# AstroEQ_Arduino_Mega.net
KiCad netlist of a schematic drawn in EAGLE
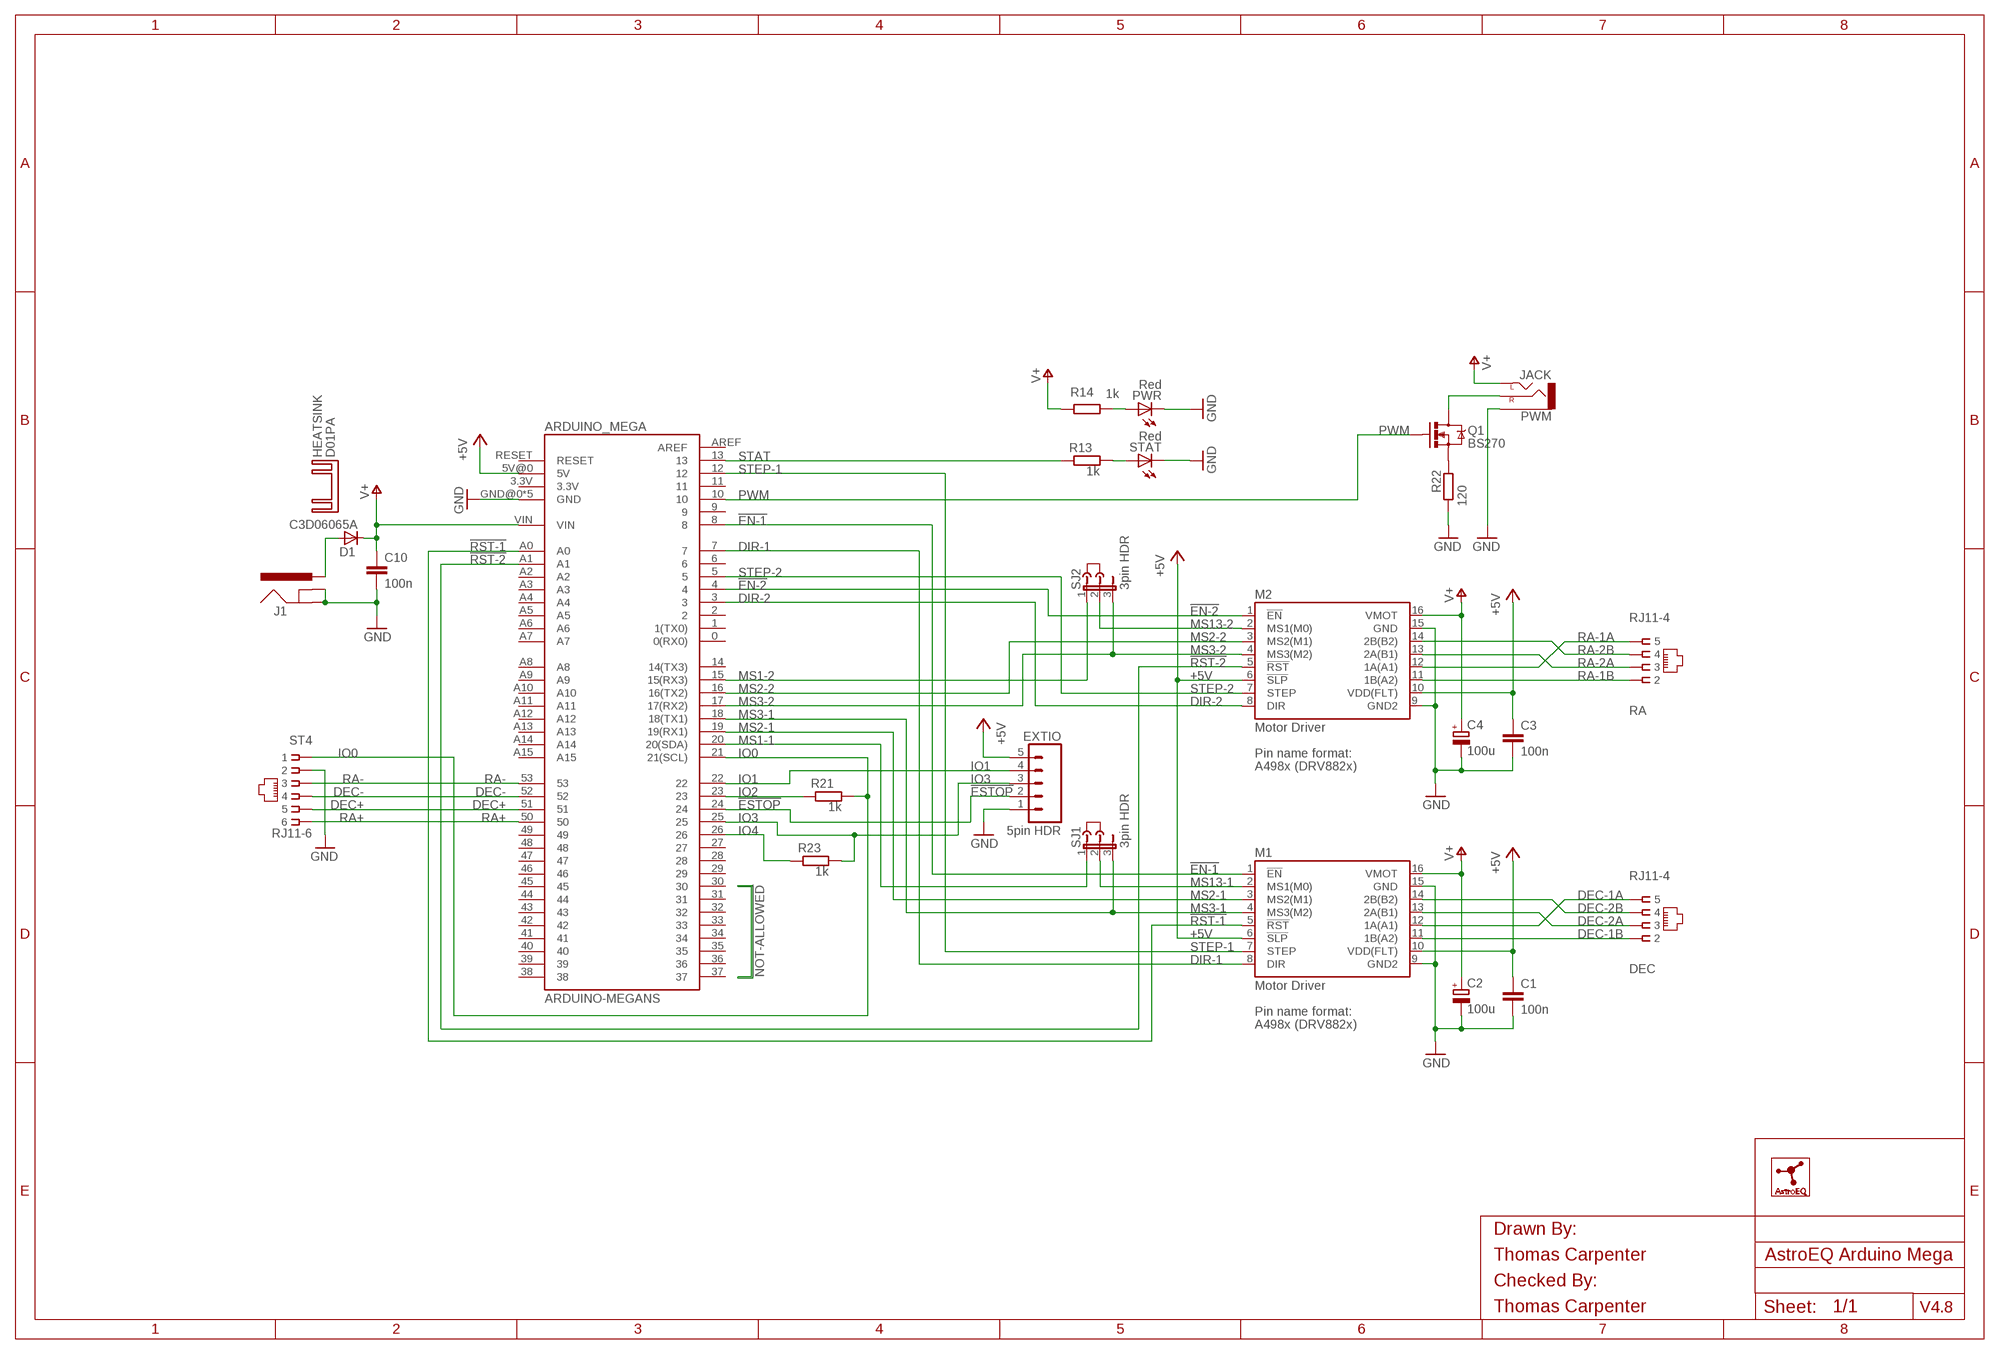
[diagram p0: schematic, sheet 1]

(export (version "E")
  (design (tool "Eeschema 10.0.6"))
  (components
    (comp (ref "ARDUINO_MEGA")
      (value "ARDUINO-MEGANS")
      (footprint "eagle-import:ARDUINO_MEGA_NS")
      (libsource (lib "eagle-import") (part "ARDUINO-MEGANS"))
    )
    (comp (ref "C1")
      (value "100n")
      (footprint "eagle-import:C025-024X044")
      (fields (field (name "MF") "AVX") (field (name "MPN") "SR205C104KAR"))
      (libsource (lib "eagle-import") (part "C-EU025-024X044"))
    )
    (comp (ref "C2")
      (value "100u")
      (footprint "eagle-import:E2,5-7")
      (fields (field (name "MF") "MULTICOMP") (field (name "MPN") "MCGPR25V107M6.3X11"))
      (libsource (lib "eagle-import") (part "CPOL-EUE2.5-7"))
    )
    (comp (ref "C3")
      (value "100n")
      (footprint "eagle-import:C025-024X044")
      (fields (field (name "MF") "AVX") (field (name "MPN") "SR205C104KAR"))
      (libsource (lib "eagle-import") (part "C-EU025-024X044"))
    )
    (comp (ref "C4")
      (value "100u")
      (footprint "eagle-import:E2,5-7")
      (fields (field (name "MF") "MULTICOMP") (field (name "MPN") "MCGPR25V107M6.3X11"))
      (libsource (lib "eagle-import") (part "CPOL-EUE2.5-7"))
    )
    (comp (ref "C10")
      (value "100n")
      (footprint "eagle-import:C025-024X044")
      (fields (field (name "MF") "AVX") (field (name "MPN") "SR205C104KAR"))
      (libsource (lib "eagle-import") (part "C-EU025-024X044"))
    )
    (comp (ref "D1")
      (value "C3D06065A")
      (footprint "eagle-import:TO220ACS")
      (fields (field (name "MF") "CREE"))
      (libsource (lib "eagle-import") (part "MUR820VERT"))
    )
    (comp (ref "DEC")
      (value "RJ11-4")
      (footprint "eagle-import:RJ11-NO_SHIELD-4")
      (fields (field (name "MF") "MOLEX") (field (name "MPN") "95501-2641"))
      (libsource (lib "eagle-import") (part "RJ11-4"))
    )
    (comp (ref "EXTIO")
      (value "5pin HDR")
      (footprint "eagle-import:1X05")
      (libsource (lib "eagle-import") (part "M05PTH"))
    )
    (comp (ref "HEATSINK")
      (value "D01PA")
      (footprint "eagle-import:D01PA")
      (libsource (lib "eagle-import") (part "D01PA"))
    )
    (comp (ref "J1")
      (value "POWER_JACKPTH")
      (footprint "eagle-import:POWER_JACK_PTH")
      (fields (field (name "MF") "MULTICOMP") (field (name "MPN") "MJ-179PH"))
      (libsource (lib "eagle-import") (part "POWER_JACKPTH"))
    )
    (comp (ref "J2")
      (value "DNI")
      (footprint "eagle-import:JUMP")
      (fields (field (name "MF") "3M") (field (name "MPN") "969102-0000-DA"))
      (libsource (lib "eagle-import") (part "JUMPER"))
    )
    (comp (ref "J3")
      (value "DNI")
      (footprint "eagle-import:JUMP")
      (fields (field (name "MF") "3M") (field (name "MPN") "969102-0000-DA"))
      (libsource (lib "eagle-import") (part "JUMPER"))
    )
    (comp (ref "LOGO1")
      (value "ASTROEQ8MM")
      (footprint "eagle-import:ASTROEQ")
      (libsource (lib "eagle-import") (part "ASTROEQ8MM"))
    )
    (comp (ref "M1")
      (value "Motor Driver")
      (footprint "eagle-import:DIP16-W")
      (fields (field (name "MF") "SAMTEC") (field (name "MPN") "CES-116-01-T-S"))
      (libsource (lib "eagle-import") (part "A4983CARRIER"))
    )
    (comp (ref "M2")
      (value "Motor Driver")
      (footprint "eagle-import:DIP16-W")
      (fields (field (name "MF") "SAMTEC") (field (name "MPN") "CES-116-01-T-S"))
      (libsource (lib "eagle-import") (part "A4983CARRIER"))
    )
    (comp (ref "PWM")
      (value "JACK")
      (footprint "eagle-import:AUDIO-JACK-3.5MM-VERT")
      (fields
        (field (name "MANUFACTURER") "LUMBERG")
        (field (name "MPN") "1502 01")
        (field (name "MF") "CLIFF ELECTRONIC COMPONENTS")
      )
      (libsource (lib "eagle-import") (part "AUDIO-JACKVERT"))
    )
    (comp (ref "PWR")
      (value "Red")
      (footprint "eagle-import:LED3MM")
      (fields (field (name "MF") "KINGBRIGHT") (field (name "MPN") "L-424HDT"))
      (libsource (lib "eagle-import") (part "LED3MM"))
    )
    (comp (ref "Q1")
      (value "BS270")
      (footprint "eagle-import:TO-92")
      (fields (field (name "MF") "FAIRCHILD SEMICONDUCTOR"))
      (libsource (lib "eagle-import") (part "MOSFET-NCHANNELPTH"))
    )
    (comp (ref "R13")
      (value "1k")
      (footprint "eagle-import:0204_5")
      (fields (field (name "MF") "MULTICOMP") (field (name "MPN") "MF12 1K"))
      (libsource (lib "eagle-import") (part "R-EU_0204/5"))
    )
    (comp (ref "R14")
      (value "1k")
      (footprint "eagle-import:0204_7")
      (fields (field (name "MF") "MULTICOMP") (field (name "MPN") "MF12 1K"))
      (libsource (lib "eagle-import") (part "R-EU_0204/7"))
    )
    (comp (ref "R21")
      (value "1k")
      (footprint "eagle-import:0204_7")
      (fields (field (name "MF") "MULTICOMP") (field (name "MPN") "MF12 1K"))
      (libsource (lib "eagle-import") (part "R-EU_0204/7"))
    )
    (comp (ref "R22")
      (value "120")
      (footprint "eagle-import:0204_7")
      (fields (field (name "MF") "MULTICOMP") (field (name "MPN") "MF12 120R"))
      (libsource (lib "eagle-import") (part "R-EU_0204/7"))
    )
    (comp (ref "R23")
      (value "1k")
      (footprint "eagle-import:0204_7")
      (fields (field (name "MF") "MULTICOMP") (field (name "MPN") "MF12 1K"))
      (libsource (lib "eagle-import") (part "R-EU_0204/7"))
    )
    (comp (ref "RA")
      (value "RJ11-4")
      (footprint "eagle-import:RJ11-NO_SHIELD-4")
      (fields (field (name "MF") "MOLEX") (field (name "MPN") "95501-2641"))
      (libsource (lib "eagle-import") (part "RJ11-4"))
    )
    (comp (ref "SJ1")
      (value "3pin HDR")
      (footprint "eagle-import:JP2")
      (fields (field (name "MF") "HARWIN") (field (name "MPN") "M20-9990345."))
      (libsource (lib "eagle-import") (part "JP2E"))
    )
    (comp (ref "SJ2")
      (value "3pin HDR")
      (footprint "eagle-import:JP2")
      (fields (field (name "MF") "HARWIN") (field (name "MPN") "M20-9990345."))
      (libsource (lib "eagle-import") (part "JP2E"))
    )
    (comp (ref "ST4")
      (value "RJ11-6")
      (footprint "eagle-import:RJ11-NO_SHIELD")
      (fields (field (name "MF") "TYCO ELECTRONICS") (field (name "MPN") "RJ11-2L-B"))
      (libsource (lib "eagle-import") (part "RJ11-2L-B"))
    )
    (comp (ref "STAT")
      (value "Red")
      (footprint "eagle-import:LED3MM")
      (fields (field (name "MF") "KINGBRIGHT") (field (name "MPN") "L-424HDT"))
      (libsource (lib "eagle-import") (part "LED3MM"))
    )
  )
  (nets
    (net (code "1") (name "+5V") (class "Default")
      (node (ref "ARDUINO_MEGA") (pin "5V@0") (pinfunction "5V_5V@0") (pintype "bidirectional"))
      (node (ref "C1") (pin "1") (pinfunction "1_1") (pintype "passive"))
      (node (ref "C3") (pin "1") (pinfunction "1_1") (pintype "passive"))
      (node (ref "EXTIO") (pin "5") (pinfunction "5_5") (pintype "passive"))
      (node (ref "M1") (pin "10") (pinfunction "VDD(FLT)_10") (pintype "power_in"))
      (node (ref "M1") (pin "6") (pinfunction "~{SLP}_6") (pintype "input"))
      (node (ref "M2") (pin "10") (pinfunction "VDD(FLT)_10") (pintype "power_in"))
      (node (ref "M2") (pin "6") (pinfunction "~{SLP}_6") (pintype "input"))
    )
    (net (code "2") (name "/DEC+") (class "Default")
      (node (ref "ARDUINO_MEGA") (pin "51") (pinfunction "51_51") (pintype "bidirectional"))
      (node (ref "ST4") (pin "5") (pinfunction "5_5") (pintype "passive"))
    )
    (net (code "3") (name "/DEC-") (class "Default")
      (node (ref "ARDUINO_MEGA") (pin "52") (pinfunction "52_52") (pintype "bidirectional"))
      (node (ref "ST4") (pin "4") (pinfunction "4_4") (pintype "passive"))
    )
    (net (code "4") (name "/DEC-1A") (class "Default")
      (node (ref "DEC") (pin "5") (pinfunction "5_5") (pintype "passive"))
      (node (ref "M1") (pin "12") (pinfunction "1A(A1)_12") (pintype "output"))
    )
    (net (code "5") (name "/DEC-1B") (class "Default")
      (node (ref "DEC") (pin "2") (pinfunction "2_2") (pintype "passive"))
      (node (ref "M1") (pin "11") (pinfunction "1B(A2)_11") (pintype "output"))
    )
    (net (code "6") (name "/DEC-2A") (class "Default")
      (node (ref "DEC") (pin "3") (pinfunction "3_3") (pintype "passive"))
      (node (ref "M1") (pin "13") (pinfunction "2A(B1)_13") (pintype "output"))
    )
    (net (code "7") (name "/DEC-2B") (class "Default")
      (node (ref "DEC") (pin "4") (pinfunction "4_4") (pintype "passive"))
      (node (ref "M1") (pin "14") (pinfunction "2B(B2)_14") (pintype "output"))
    )
    (net (code "8") (name "/DIR-1") (class "Default")
      (node (ref "ARDUINO_MEGA") (pin "7") (pinfunction "7_7") (pintype "bidirectional"))
      (node (ref "M1") (pin "8") (pinfunction "DIR_8") (pintype "input"))
    )
    (net (code "9") (name "/DIR-2") (class "Default")
      (node (ref "ARDUINO_MEGA") (pin "3") (pinfunction "3_3") (pintype "bidirectional"))
      (node (ref "M2") (pin "8") (pinfunction "DIR_8") (pintype "input"))
    )
    (net (code "10") (name "/IO0") (class "Default")
      (node (ref "ARDUINO_MEGA") (pin "21") (pinfunction "21(SCL)_21") (pintype "bidirectional"))
      (node (ref "R21") (pin "2") (pinfunction "2_2") (pintype "passive"))
      (node (ref "ST4") (pin "1") (pinfunction "1_1") (pintype "passive"))
    )
    (net (code "11") (name "/IO1") (class "Default")
      (node (ref "ARDUINO_MEGA") (pin "22") (pinfunction "22_22") (pintype "bidirectional"))
      (node (ref "EXTIO") (pin "4") (pinfunction "4_4") (pintype "passive"))
    )
    (net (code "12") (name "/IO2") (class "Default")
      (node (ref "ARDUINO_MEGA") (pin "23") (pinfunction "23_23") (pintype "bidirectional"))
      (node (ref "R21") (pin "1") (pinfunction "1_1") (pintype "passive"))
    )
    (net (code "13") (name "/IO3") (class "Default")
      (node (ref "ARDUINO_MEGA") (pin "25") (pinfunction "25_25") (pintype "bidirectional"))
      (node (ref "EXTIO") (pin "3") (pinfunction "3_3") (pintype "passive"))
      (node (ref "R23") (pin "2") (pinfunction "2_2") (pintype "passive"))
    )
    (net (code "14") (name "/IO4") (class "Default")
      (node (ref "ARDUINO_MEGA") (pin "26") (pinfunction "26_26") (pintype "bidirectional"))
      (node (ref "R23") (pin "1") (pinfunction "1_1") (pintype "passive"))
    )
    (net (code "15") (name "/MS1-1") (class "Default")
      (node (ref "ARDUINO_MEGA") (pin "20") (pinfunction "20(SDA)_20") (pintype "bidirectional"))
      (node (ref "SJ1") (pin "1") (pinfunction "1_1") (pintype "passive"))
    )
    (net (code "16") (name "/MS1-2") (class "Default")
      (node (ref "ARDUINO_MEGA") (pin "15") (pinfunction "15(RX3)_15") (pintype "bidirectional"))
      (node (ref "SJ2") (pin "1") (pinfunction "1_1") (pintype "passive"))
    )
    (net (code "17") (name "/MS2-1") (class "Default")
      (node (ref "ARDUINO_MEGA") (pin "19") (pinfunction "19(RX1)_19") (pintype "bidirectional"))
      (node (ref "M1") (pin "3") (pinfunction "MS2(M1)_3") (pintype "input"))
    )
    (net (code "18") (name "/MS2-2") (class "Default")
      (node (ref "ARDUINO_MEGA") (pin "16") (pinfunction "16(TX2)_16") (pintype "bidirectional"))
      (node (ref "M2") (pin "3") (pinfunction "MS2(M1)_3") (pintype "input"))
    )
    (net (code "19") (name "/MS3-1") (class "Default")
      (node (ref "ARDUINO_MEGA") (pin "18") (pinfunction "18(TX1)_18") (pintype "bidirectional"))
      (node (ref "M1") (pin "4") (pinfunction "MS3(M2)_4") (pintype "input"))
      (node (ref "SJ1") (pin "3") (pinfunction "3_3") (pintype "passive"))
    )
    (net (code "20") (name "/MS3-2") (class "Default")
      (node (ref "ARDUINO_MEGA") (pin "17") (pinfunction "17(RX2)_17") (pintype "bidirectional"))
      (node (ref "M2") (pin "4") (pinfunction "MS3(M2)_4") (pintype "input"))
      (node (ref "SJ2") (pin "3") (pinfunction "3_3") (pintype "passive"))
    )
    (net (code "21") (name "/MS13-1") (class "Default")
      (node (ref "M1") (pin "2") (pinfunction "MS1(M0)_2") (pintype "input"))
      (node (ref "SJ1") (pin "2") (pinfunction "2_2") (pintype "passive"))
    )
    (net (code "22") (name "/MS13-2") (class "Default")
      (node (ref "M2") (pin "2") (pinfunction "MS1(M0)_2") (pintype "input"))
      (node (ref "SJ2") (pin "2") (pinfunction "2_2") (pintype "passive"))
    )
    (net (code "23") (name "/PWM") (class "Default")
      (node (ref "ARDUINO_MEGA") (pin "10") (pinfunction "10_10") (pintype "bidirectional"))
      (node (ref "Q1") (pin "2") (pinfunction "G_2") (pintype "passive"))
    )
    (net (code "24") (name "/RA+") (class "Default")
      (node (ref "ARDUINO_MEGA") (pin "50") (pinfunction "50_50") (pintype "bidirectional"))
      (node (ref "ST4") (pin "6") (pinfunction "6_6") (pintype "passive"))
    )
    (net (code "25") (name "/RA-") (class "Default")
      (node (ref "ARDUINO_MEGA") (pin "53") (pinfunction "53_53") (pintype "bidirectional"))
      (node (ref "ST4") (pin "3") (pinfunction "3_3") (pintype "passive"))
    )
    (net (code "26") (name "/RA-1A") (class "Default")
      (node (ref "M2") (pin "12") (pinfunction "1A(A1)_12") (pintype "output"))
      (node (ref "RA") (pin "5") (pinfunction "5_5") (pintype "passive"))
    )
    (net (code "27") (name "/RA-1B") (class "Default")
      (node (ref "M2") (pin "11") (pinfunction "1B(A2)_11") (pintype "output"))
      (node (ref "RA") (pin "2") (pinfunction "2_2") (pintype "passive"))
    )
    (net (code "28") (name "/RA-2A") (class "Default")
      (node (ref "M2") (pin "13") (pinfunction "2A(B1)_13") (pintype "output"))
      (node (ref "RA") (pin "3") (pinfunction "3_3") (pintype "passive"))
    )
    (net (code "29") (name "/RA-2B") (class "Default")
      (node (ref "M2") (pin "14") (pinfunction "2B(B2)_14") (pintype "output"))
      (node (ref "RA") (pin "4") (pinfunction "4_4") (pintype "passive"))
    )
    (net (code "30") (name "/STAT") (class "Default")
      (node (ref "ARDUINO_MEGA") (pin "13") (pinfunction "13_13") (pintype "bidirectional"))
      (node (ref "R13") (pin "1") (pinfunction "1_1") (pintype "passive"))
    )
    (net (code "31") (name "/STEP-1") (class "Default")
      (node (ref "ARDUINO_MEGA") (pin "12") (pinfunction "12_12") (pintype "bidirectional"))
      (node (ref "M1") (pin "7") (pinfunction "STEP_7") (pintype "input"))
    )
    (net (code "32") (name "/STEP-2") (class "Default")
      (node (ref "ARDUINO_MEGA") (pin "5") (pinfunction "5_5") (pintype "bidirectional"))
      (node (ref "M2") (pin "7") (pinfunction "STEP_7") (pintype "input"))
    )
    (net (code "33") (name "/~{EN-1}") (class "Default")
      (node (ref "ARDUINO_MEGA") (pin "8") (pinfunction "8_8") (pintype "bidirectional"))
      (node (ref "M1") (pin "1") (pinfunction "~{EN}_1") (pintype "input"))
    )
    (net (code "34") (name "/~{EN-2}") (class "Default")
      (node (ref "ARDUINO_MEGA") (pin "4") (pinfunction "4_4") (pintype "bidirectional"))
      (node (ref "M2") (pin "1") (pinfunction "~{EN}_1") (pintype "input"))
    )
    (net (code "35") (name "/~{ESTOP}") (class "Default")
      (node (ref "ARDUINO_MEGA") (pin "24") (pinfunction "24_24") (pintype "bidirectional"))
      (node (ref "EXTIO") (pin "2") (pinfunction "2_2") (pintype "passive"))
    )
    (net (code "37") (name "/~{RST-1}") (class "Default")
      (node (ref "ARDUINO_MEGA") (pin "A0") (pinfunction "A0_A0") (pintype "bidirectional"))
      (node (ref "M1") (pin "5") (pinfunction "~{RST}_5") (pintype "input"))
    )
    (net (code "38") (name "/~{RST-2}") (class "Default")
      (node (ref "ARDUINO_MEGA") (pin "A1") (pinfunction "A1_A1") (pintype "bidirectional"))
      (node (ref "M2") (pin "5") (pinfunction "~{RST}_5") (pintype "input"))
    )
    (net (code "39") (name "GND") (class "Default")
      (node (ref "ARDUINO_MEGA") (pin "GND@0") (pinfunction "GND_GND@0") (pintype "bidirectional"))
      (node (ref "ARDUINO_MEGA") (pin "GND@1") (pinfunction "GND_GND@1") (pintype "bidirectional"))
      (node (ref "ARDUINO_MEGA") (pin "GND@2") (pinfunction "GND_GND@2") (pintype "bidirectional"))
      (node (ref "ARDUINO_MEGA") (pin "GND@3") (pinfunction "GND_GND@3") (pintype "bidirectional"))
      (node (ref "ARDUINO_MEGA") (pin "GND@4") (pinfunction "GND_GND@4") (pintype "bidirectional"))
      (node (ref "C1") (pin "2") (pinfunction "2_2") (pintype "passive"))
      (node (ref "C10") (pin "2") (pinfunction "2_2") (pintype "passive"))
      (node (ref "C2") (pin "-") (pinfunction "-_-") (pintype "passive"))
      (node (ref "C3") (pin "2") (pinfunction "2_2") (pintype "passive"))
      (node (ref "C4") (pin "-") (pinfunction "-_-") (pintype "passive"))
      (node (ref "EXTIO") (pin "1") (pinfunction "1_1") (pintype "passive"))
      (node (ref "J1") (pin "GND") (pinfunction "GND_GND") (pintype "bidirectional"))
      (node (ref "J1") (pin "GNDBREAK") (pinfunction "GNDBREAK_GNDBREAK") (pintype "bidirectional"))
      (node (ref "M1") (pin "15") (pinfunction "GND_15") (pintype "power_in"))
      (node (ref "M1") (pin "9") (pinfunction "GND2_9") (pintype "power_in"))
      (node (ref "M2") (pin "15") (pinfunction "GND_15") (pintype "power_in"))
      (node (ref "M2") (pin "9") (pinfunction "GND2_9") (pintype "power_in"))
      (node (ref "PWM") (pin "1") (pinfunction "SLEEVE_1") (pintype "bidirectional"))
      (node (ref "PWR") (pin "K") (pinfunction "C_K") (pintype "passive"))
      (node (ref "R22") (pin "1") (pinfunction "1_1") (pintype "passive"))
      (node (ref "ST4") (pin "2") (pinfunction "2_2") (pintype "passive"))
      (node (ref "STAT") (pin "K") (pinfunction "C_K") (pintype "passive"))
    )
    (net (code "40") (name "Net-(D1-PadA)") (class "Default")
      (node (ref "D1") (pin "A") (pinfunction "A_A") (pintype "passive"))
      (node (ref "J1") (pin "PWR") (pinfunction "PWR_PWR") (pintype "bidirectional"))
    )
    (net (code "41") (name "Net-(PWM-RIGHT)") (class "Default")
      (node (ref "PWM") (pin "3") (pinfunction "RIGHT_3") (pintype "bidirectional"))
      (node (ref "Q1") (pin "1") (pinfunction "D_1") (pintype "passive"))
    )
    (net (code "42") (name "Net-(PWR-PadA)") (class "Default")
      (node (ref "PWR") (pin "A") (pinfunction "A_A") (pintype "passive"))
      (node (ref "R14") (pin "2") (pinfunction "2_2") (pintype "passive"))
    )
    (net (code "43") (name "Net-(Q1-S)") (class "Default")
      (node (ref "Q1") (pin "3") (pinfunction "S_3") (pintype "passive"))
      (node (ref "R22") (pin "2") (pinfunction "2_2") (pintype "passive"))
    )
    (net (code "44") (name "Net-(R13-Pad2)") (class "Default")
      (node (ref "R13") (pin "2") (pinfunction "2_2") (pintype "passive"))
      (node (ref "STAT") (pin "A") (pinfunction "A_A") (pintype "passive"))
    )
    (net (code "45") (name "V+") (class "Default")
      (node (ref "ARDUINO_MEGA") (pin "VIN") (pinfunction "VIN_VIN") (pintype "bidirectional"))
      (node (ref "C10") (pin "1") (pinfunction "1_1") (pintype "passive"))
      (node (ref "C2") (pin "+") (pinfunction "+_+") (pintype "passive"))
      (node (ref "C4") (pin "+") (pinfunction "+_+") (pintype "passive"))
      (node (ref "D1") (pin "C") (pinfunction "C_C") (pintype "passive"))
      (node (ref "M1") (pin "16") (pinfunction "VMOT_16") (pintype "power_in"))
      (node (ref "M2") (pin "16") (pinfunction "VMOT_16") (pintype "power_in"))
      (node (ref "PWM") (pin "2") (pinfunction "LEFT_2") (pintype "bidirectional"))
      (node (ref "R14") (pin "1") (pinfunction "1_1") (pintype "passive"))
    )
    (net (code "46") (name "unconnected-(ARDUINO_MEGA-0(RX0)-Pad0)") (class "Default")
      (node (ref "ARDUINO_MEGA") (pin "0") (pinfunction "0(RX0)_0") (pintype "bidirectional"))
    )
    (net (code "47") (name "unconnected-(ARDUINO_MEGA-1(TX0)-Pad1)") (class "Default")
      (node (ref "ARDUINO_MEGA") (pin "1") (pinfunction "1(TX0)_1") (pintype "bidirectional"))
    )
    (net (code "48") (name "unconnected-(ARDUINO_MEGA-14(TX3)-Pad14)") (class "Default")
      (node (ref "ARDUINO_MEGA") (pin "14") (pinfunction "14(TX3)_14") (pintype "bidirectional"))
    )
    (net (code "49") (name "unconnected-(ARDUINO_MEGA-Pad2)") (class "Default")
      (node (ref "ARDUINO_MEGA") (pin "2") (pinfunction "2_2") (pintype "bidirectional"))
    )
    (net (code "50") (name "unconnected-(ARDUINO_MEGA-Pad3.3V)") (class "Default")
      (node (ref "ARDUINO_MEGA") (pin "3.3V") (pinfunction "3.3V_3.3V") (pintype "bidirectional"))
    )
    (net (code "51") (name "unconnected-(ARDUINO_MEGA-Pad6)") (class "Default")
      (node (ref "ARDUINO_MEGA") (pin "6") (pinfunction "6_6") (pintype "bidirectional"))
    )
    (net (code "52") (name "unconnected-(ARDUINO_MEGA-Pad9)") (class "Default")
      (node (ref "ARDUINO_MEGA") (pin "9") (pinfunction "9_9") (pintype "bidirectional"))
    )
    (net (code "53") (name "unconnected-(ARDUINO_MEGA-Pad11)") (class "Default")
      (node (ref "ARDUINO_MEGA") (pin "11") (pinfunction "11_11") (pintype "bidirectional"))
    )
    (net (code "54") (name "unconnected-(ARDUINO_MEGA-Pad27)") (class "Default")
      (node (ref "ARDUINO_MEGA") (pin "27") (pinfunction "27_27") (pintype "bidirectional"))
    )
    (net (code "55") (name "unconnected-(ARDUINO_MEGA-Pad28)") (class "Default")
      (node (ref "ARDUINO_MEGA") (pin "28") (pinfunction "28_28") (pintype "bidirectional"))
    )
    (net (code "56") (name "unconnected-(ARDUINO_MEGA-Pad29)") (class "Default")
      (node (ref "ARDUINO_MEGA") (pin "29") (pinfunction "29_29") (pintype "bidirectional"))
    )
    (net (code "57") (name "unconnected-(ARDUINO_MEGA-Pad30)") (class "Default")
      (node (ref "ARDUINO_MEGA") (pin "30") (pinfunction "30_30") (pintype "bidirectional"))
    )
    (net (code "58") (name "unconnected-(ARDUINO_MEGA-Pad31)") (class "Default")
      (node (ref "ARDUINO_MEGA") (pin "31") (pinfunction "31_31") (pintype "bidirectional"))
    )
    (net (code "59") (name "unconnected-(ARDUINO_MEGA-Pad32)") (class "Default")
      (node (ref "ARDUINO_MEGA") (pin "32") (pinfunction "32_32") (pintype "bidirectional"))
    )
    (net (code "60") (name "unconnected-(ARDUINO_MEGA-Pad33)") (class "Default")
      (node (ref "ARDUINO_MEGA") (pin "33") (pinfunction "33_33") (pintype "bidirectional"))
    )
    (net (code "61") (name "unconnected-(ARDUINO_MEGA-Pad34)") (class "Default")
      (node (ref "ARDUINO_MEGA") (pin "34") (pinfunction "34_34") (pintype "bidirectional"))
    )
    (net (code "62") (name "unconnected-(ARDUINO_MEGA-Pad35)") (class "Default")
      (node (ref "ARDUINO_MEGA") (pin "35") (pinfunction "35_35") (pintype "bidirectional"))
    )
    (net (code "63") (name "unconnected-(ARDUINO_MEGA-Pad36)") (class "Default")
      (node (ref "ARDUINO_MEGA") (pin "36") (pinfunction "36_36") (pintype "bidirectional"))
    )
    (net (code "64") (name "unconnected-(ARDUINO_MEGA-Pad37)") (class "Default")
      (node (ref "ARDUINO_MEGA") (pin "37") (pinfunction "37_37") (pintype "bidirectional"))
    )
    (net (code "65") (name "unconnected-(ARDUINO_MEGA-Pad38)") (class "Default")
      (node (ref "ARDUINO_MEGA") (pin "38") (pinfunction "38_38") (pintype "bidirectional"))
    )
    (net (code "66") (name "unconnected-(ARDUINO_MEGA-Pad39)") (class "Default")
      (node (ref "ARDUINO_MEGA") (pin "39") (pinfunction "39_39") (pintype "bidirectional"))
    )
    (net (code "67") (name "unconnected-(ARDUINO_MEGA-Pad40)") (class "Default")
      (node (ref "ARDUINO_MEGA") (pin "40") (pinfunction "40_40") (pintype "bidirectional"))
    )
    (net (code "68") (name "unconnected-(ARDUINO_MEGA-Pad41)") (class "Default")
      (node (ref "ARDUINO_MEGA") (pin "41") (pinfunction "41_41") (pintype "bidirectional"))
    )
    (net (code "69") (name "unconnected-(ARDUINO_MEGA-Pad42)") (class "Default")
      (node (ref "ARDUINO_MEGA") (pin "42") (pinfunction "42_42") (pintype "bidirectional"))
    )
    (net (code "70") (name "unconnected-(ARDUINO_MEGA-Pad43)") (class "Default")
      (node (ref "ARDUINO_MEGA") (pin "43") (pinfunction "43_43") (pintype "bidirectional"))
    )
    (net (code "71") (name "unconnected-(ARDUINO_MEGA-Pad44)") (class "Default")
      (node (ref "ARDUINO_MEGA") (pin "44") (pinfunction "44_44") (pintype "bidirectional"))
    )
    (net (code "72") (name "unconnected-(ARDUINO_MEGA-Pad45)") (class "Default")
      (node (ref "ARDUINO_MEGA") (pin "45") (pinfunction "45_45") (pintype "bidirectional"))
    )
    (net (code "73") (name "unconnected-(ARDUINO_MEGA-Pad46)") (class "Default")
      (node (ref "ARDUINO_MEGA") (pin "46") (pinfunction "46_46") (pintype "bidirectional"))
    )
    (net (code "74") (name "unconnected-(ARDUINO_MEGA-Pad47)") (class "Default")
      (node (ref "ARDUINO_MEGA") (pin "47") (pinfunction "47_47") (pintype "bidirectional"))
    )
    (net (code "75") (name "unconnected-(ARDUINO_MEGA-Pad48)") (class "Default")
      (node (ref "ARDUINO_MEGA") (pin "48") (pinfunction "48_48") (pintype "bidirectional"))
    )
    (net (code "76") (name "unconnected-(ARDUINO_MEGA-Pad49)") (class "Default")
      (node (ref "ARDUINO_MEGA") (pin "49") (pinfunction "49_49") (pintype "bidirectional"))
    )
    (net (code "77") (name "unconnected-(ARDUINO_MEGA-PadA2)") (class "Default")
      (node (ref "ARDUINO_MEGA") (pin "A2") (pinfunction "A2_A2") (pintype "bidirectional"))
    )
    (net (code "78") (name "unconnected-(ARDUINO_MEGA-PadA3)") (class "Default")
      (node (ref "ARDUINO_MEGA") (pin "A3") (pinfunction "A3_A3") (pintype "bidirectional"))
    )
    (net (code "79") (name "unconnected-(ARDUINO_MEGA-PadA4)") (class "Default")
      (node (ref "ARDUINO_MEGA") (pin "A4") (pinfunction "A4_A4") (pintype "bidirectional"))
    )
    (net (code "80") (name "unconnected-(ARDUINO_MEGA-PadA5)") (class "Default")
      (node (ref "ARDUINO_MEGA") (pin "A5") (pinfunction "A5_A5") (pintype "bidirectional"))
    )
    (net (code "81") (name "unconnected-(ARDUINO_MEGA-PadA6)") (class "Default")
      (node (ref "ARDUINO_MEGA") (pin "A6") (pinfunction "A6_A6") (pintype "bidirectional"))
    )
    (net (code "82") (name "unconnected-(ARDUINO_MEGA-PadA7)") (class "Default")
      (node (ref "ARDUINO_MEGA") (pin "A7") (pinfunction "A7_A7") (pintype "bidirectional"))
    )
    (net (code "83") (name "unconnected-(ARDUINO_MEGA-PadA8)") (class "Default")
      (node (ref "ARDUINO_MEGA") (pin "A8") (pinfunction "A8_A8") (pintype "bidirectional"))
    )
    (net (code "84") (name "unconnected-(ARDUINO_MEGA-PadA9)") (class "Default")
      (node (ref "ARDUINO_MEGA") (pin "A9") (pinfunction "A9_A9") (pintype "bidirectional"))
    )
    (net (code "85") (name "unconnected-(ARDUINO_MEGA-PadA10)") (class "Default")
      (node (ref "ARDUINO_MEGA") (pin "A10") (pinfunction "A10_A10") (pintype "bidirectional"))
    )
    (net (code "86") (name "unconnected-(ARDUINO_MEGA-PadA11)") (class "Default")
      (node (ref "ARDUINO_MEGA") (pin "A11") (pinfunction "A11_A11") (pintype "bidirectional"))
    )
    (net (code "87") (name "unconnected-(ARDUINO_MEGA-PadA12)") (class "Default")
      (node (ref "ARDUINO_MEGA") (pin "A12") (pinfunction "A12_A12") (pintype "bidirectional"))
    )
    (net (code "88") (name "unconnected-(ARDUINO_MEGA-PadA13)") (class "Default")
      (node (ref "ARDUINO_MEGA") (pin "A13") (pinfunction "A13_A13") (pintype "bidirectional"))
    )
    (net (code "89") (name "unconnected-(ARDUINO_MEGA-PadA14)") (class "Default")
      (node (ref "ARDUINO_MEGA") (pin "A14") (pinfunction "A14_A14") (pintype "bidirectional"))
    )
    (net (code "90") (name "unconnected-(ARDUINO_MEGA-PadA15)") (class "Default")
      (node (ref "ARDUINO_MEGA") (pin "A15") (pinfunction "A15_A15") (pintype "bidirectional"))
    )
    (net (code "91") (name "unconnected-(ARDUINO_MEGA-PadAREF)") (class "Default")
      (node (ref "ARDUINO_MEGA") (pin "AREF") (pinfunction "AREF_AREF") (pintype "bidirectional"))
    )
    (net (code "92") (name "unconnected-(ARDUINO_MEGA-PadRESET)") (class "Default")
      (node (ref "ARDUINO_MEGA") (pin "RESET") (pinfunction "RESET_RESET") (pintype "bidirectional"))
    )
  )
)
